# pusher.net
KiCad netlist of a schematic drawn in EAGLE
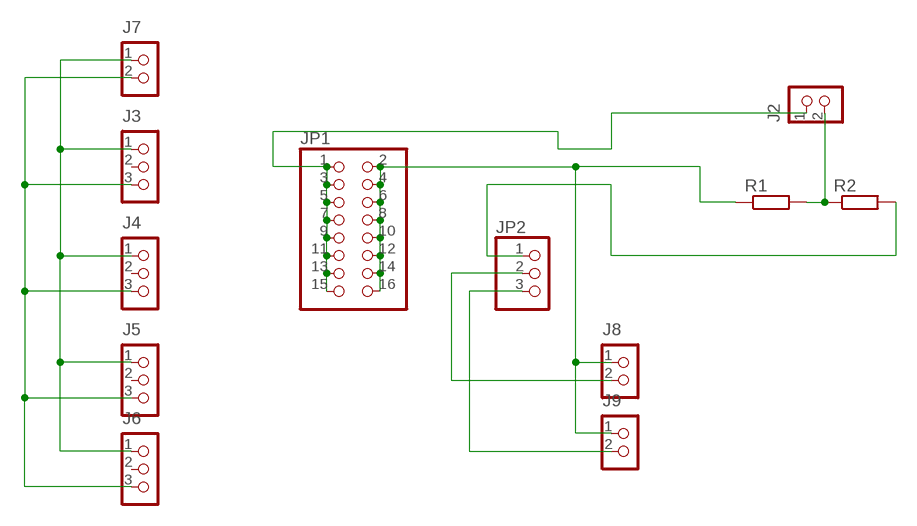
[diagram p0: schematic, sheet 1]

(export (version "E")
  (design (tool "Eeschema 10.0.6"))
  (components
    (comp (ref "J2")
      (value "CON_TERMINAL_BLOCK_02-5MM")
      (footprint "eagle-import:TERMINAL_BLOCK_2P_5")
      (libsource (lib "eagle-import") (part "dp_devices.v6_CON_TERMINAL_BLOCK_02-5MM"))
    )
    (comp (ref "J3")
      (value "CON_TERMINAL_BLOCK_03-5MM")
      (footprint "eagle-import:TERMINAL_BLOCK_3P_5")
      (libsource (lib "eagle-import") (part "CON_TERMINAL_BLOCK_03-5MM"))
    )
    (comp (ref "J4")
      (value "CON_TERMINAL_BLOCK_03-5MM")
      (footprint "eagle-import:TERMINAL_BLOCK_3P_5")
      (libsource (lib "eagle-import") (part "CON_TERMINAL_BLOCK_03-5MM"))
    )
    (comp (ref "J5")
      (value "CON_TERMINAL_BLOCK_03-5MM")
      (footprint "eagle-import:TERMINAL_BLOCK_3P_5")
      (libsource (lib "eagle-import") (part "CON_TERMINAL_BLOCK_03-5MM"))
    )
    (comp (ref "J6")
      (value "CON_TERMINAL_BLOCK_03-5MM")
      (footprint "eagle-import:TERMINAL_BLOCK_3P_5")
      (libsource (lib "eagle-import") (part "CON_TERMINAL_BLOCK_03-5MM"))
    )
    (comp (ref "J7")
      (value "CON_TERMINAL_BLOCK_02-5MM")
      (footprint "eagle-import:TERMINAL_BLOCK_2P_5")
      (libsource (lib "eagle-import") (part "CON_TERMINAL_BLOCK_02-5MM"))
    )
    (comp (ref "J8")
      (value "CON_TERMINAL_BLOCK_02-5MM")
      (footprint "eagle-import:TERMINAL_BLOCK_2P_5")
      (libsource (lib "eagle-import") (part "dp_devices.v6_CON_TERMINAL_BLOCK_02-5MM"))
    )
    (comp (ref "J9")
      (value "CON_TERMINAL_BLOCK_02-5MM")
      (footprint "eagle-import:TERMINAL_BLOCK_2P_5")
      (libsource (lib "eagle-import") (part "dp_devices.v6_CON_TERMINAL_BLOCK_02-5MM"))
    )
    (comp (ref "JP1")
      (value "PINHD-2X8")
      (footprint "eagle-import:2X08")
      (libsource (lib "eagle-import") (part "PINHD-2X8"))
    )
    (comp (ref "JP2")
      (value "PINHD-1X3")
      (footprint "eagle-import:1X03")
      (libsource (lib "eagle-import") (part "PINHD-1X3"))
    )
    (comp (ref "R1")
      (value "R-EU_0207/10")
      (footprint "eagle-import:0207_10")
      (libsource (lib "eagle-import") (part "R-EU_0207/10"))
    )
    (comp (ref "R2")
      (value "R-EU_0207/10")
      (footprint "eagle-import:0207_10")
      (libsource (lib "eagle-import") (part "R-EU_0207/10"))
    )
  )
  (nets
    (net (code "1") (name "Net-(J2-Pad1)") (class "Default")
      (node (ref "J2") (pin "1") (pinfunction "1_1") (pintype "passive"))
      (node (ref "JP1") (pin "1") (pinfunction "1_1") (pintype "passive"))
      (node (ref "JP1") (pin "11") (pinfunction "11_11") (pintype "passive"))
      (node (ref "JP1") (pin "13") (pinfunction "13_13") (pintype "passive"))
      (node (ref "JP1") (pin "15") (pinfunction "15_15") (pintype "passive"))
      (node (ref "JP1") (pin "3") (pinfunction "3_3") (pintype "passive"))
      (node (ref "JP1") (pin "5") (pinfunction "5_5") (pintype "passive"))
      (node (ref "JP1") (pin "7") (pinfunction "7_7") (pintype "passive"))
      (node (ref "JP1") (pin "9") (pinfunction "9_9") (pintype "passive"))
    )
    (net (code "2") (name "Net-(J2-Pad2)") (class "Default")
      (node (ref "J2") (pin "2") (pinfunction "2_2") (pintype "passive"))
      (node (ref "R1") (pin "2") (pinfunction "2_2") (pintype "passive"))
      (node (ref "R2") (pin "1") (pinfunction "1_1") (pintype "passive"))
    )
    (net (code "3") (name "Net-(J3-Pad1)") (class "Default")
      (node (ref "J3") (pin "1") (pinfunction "1_1") (pintype "bidirectional"))
      (node (ref "J4") (pin "1") (pinfunction "1_1") (pintype "bidirectional"))
      (node (ref "J5") (pin "1") (pinfunction "1_1") (pintype "bidirectional"))
      (node (ref "J6") (pin "1") (pinfunction "1_1") (pintype "bidirectional"))
      (node (ref "J7") (pin "1") (pinfunction "1_1") (pintype "passive"))
    )
    (net (code "4") (name "Net-(J3-Pad3)") (class "Default")
      (node (ref "J3") (pin "3") (pinfunction "3_3") (pintype "bidirectional"))
      (node (ref "J4") (pin "3") (pinfunction "3_3") (pintype "bidirectional"))
      (node (ref "J5") (pin "3") (pinfunction "3_3") (pintype "bidirectional"))
      (node (ref "J6") (pin "3") (pinfunction "3_3") (pintype "bidirectional"))
      (node (ref "J7") (pin "2") (pinfunction "2_2") (pintype "passive"))
    )
    (net (code "5") (name "Net-(J8-Pad1)") (class "Default")
      (node (ref "J8") (pin "1") (pinfunction "1_1") (pintype "passive"))
      (node (ref "J9") (pin "1") (pinfunction "1_1") (pintype "passive"))
      (node (ref "JP1") (pin "10") (pinfunction "10_10") (pintype "passive"))
      (node (ref "JP1") (pin "12") (pinfunction "12_12") (pintype "passive"))
      (node (ref "JP1") (pin "14") (pinfunction "14_14") (pintype "passive"))
      (node (ref "JP1") (pin "16") (pinfunction "16_16") (pintype "passive"))
      (node (ref "JP1") (pin "2") (pinfunction "2_2") (pintype "passive"))
      (node (ref "JP1") (pin "4") (pinfunction "4_4") (pintype "passive"))
      (node (ref "JP1") (pin "6") (pinfunction "6_6") (pintype "passive"))
      (node (ref "JP1") (pin "8") (pinfunction "8_8") (pintype "passive"))
      (node (ref "R1") (pin "1") (pinfunction "1_1") (pintype "passive"))
    )
    (net (code "6") (name "Net-(J8-Pad2)") (class "Default")
      (node (ref "J8") (pin "2") (pinfunction "2_2") (pintype "passive"))
      (node (ref "JP2") (pin "2") (pinfunction "2_2") (pintype "passive"))
    )
    (net (code "7") (name "Net-(J9-Pad2)") (class "Default")
      (node (ref "J9") (pin "2") (pinfunction "2_2") (pintype "passive"))
      (node (ref "JP2") (pin "3") (pinfunction "3_3") (pintype "passive"))
    )
    (net (code "8") (name "Net-(JP2-Pad1)") (class "Default")
      (node (ref "JP2") (pin "1") (pinfunction "1_1") (pintype "passive"))
      (node (ref "R2") (pin "2") (pinfunction "2_2") (pintype "passive"))
    )
    (net (code "9") (name "unconnected-(J3-Pad2)") (class "Default")
      (node (ref "J3") (pin "2") (pinfunction "2_2") (pintype "bidirectional"))
    )
    (net (code "10") (name "unconnected-(J4-Pad2)") (class "Default")
      (node (ref "J4") (pin "2") (pinfunction "2_2") (pintype "bidirectional"))
    )
    (net (code "11") (name "unconnected-(J5-Pad2)") (class "Default")
      (node (ref "J5") (pin "2") (pinfunction "2_2") (pintype "bidirectional"))
    )
    (net (code "12") (name "unconnected-(J6-Pad2)") (class "Default")
      (node (ref "J6") (pin "2") (pinfunction "2_2") (pintype "bidirectional"))
    )
  )
)
